# LDO-Board.net
KiCad netlist of a schematic drawn in Altium Designer
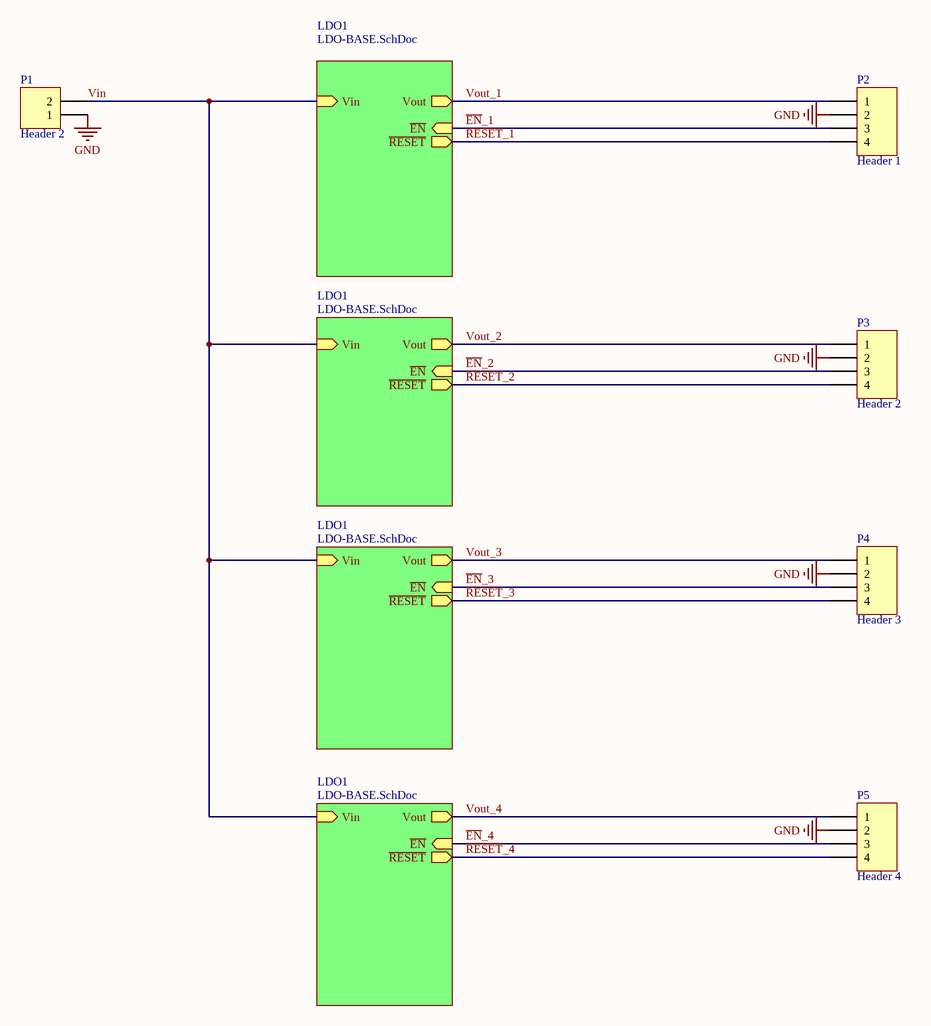
[diagram p0: LDO-Board.SchDoc]

(export (version "E")
  (design (tool "Eeschema 10.0.6"))
  (components
    (comp (ref "P1")
      (value "Header 2")
      (footprint "HDR1X2")
      (description "Header, 2-Pin")
      (fields (field (name "PUBLISHER") "Altium Limited"))
      (libsource (lib "Miscellaneous Connectors") (part "Header 2"))
    )
    (comp (ref "P2")
      (value "Header 1")
      (footprint "HDR1X4")
      (description "Header, 4-Pin")
      (fields (field (name "PUBLISHER") "Altium Limited"))
      (libsource (lib "Miscellaneous Connectors") (part "Header 4"))
    )
    (comp (ref "P3")
      (value "Header 2")
      (footprint "HDR1X4")
      (description "Header, 4-Pin")
      (fields (field (name "PUBLISHER") "Altium Limited"))
      (libsource (lib "Miscellaneous Connectors") (part "Header 4"))
    )
    (comp (ref "P4")
      (value "Header 3")
      (footprint "HDR1X4")
      (description "Header, 4-Pin")
      (fields (field (name "PUBLISHER") "Altium Limited"))
      (libsource (lib "Miscellaneous Connectors") (part "Header 4"))
    )
    (comp (ref "P5")
      (value "Header 4")
      (footprint "HDR1X4")
      (description "Header, 4-Pin")
      (fields (field (name "PUBLISHER") "Altium Limited"))
      (libsource (lib "Miscellaneous Connectors") (part "Header 4"))
    )
  )
  (nets
    (net (code "1") (name "/Vin") (class "Default")
      (node (ref "P1") (pin "2") (pinfunction "2_2") (pintype "passive"))
    )
    (net (code "2") (name "/Vout_1") (class "Default")
      (node (ref "P2") (pin "1") (pinfunction "1_1") (pintype "passive"))
    )
    (net (code "3") (name "/Vout_2") (class "Default")
      (node (ref "P3") (pin "1") (pinfunction "1_1") (pintype "passive"))
    )
    (net (code "4") (name "/Vout_3") (class "Default")
      (node (ref "P4") (pin "1") (pinfunction "1_1") (pintype "passive"))
    )
    (net (code "5") (name "/Vout_4") (class "Default")
      (node (ref "P5") (pin "1") (pinfunction "1_1") (pintype "passive"))
    )
    (net (code "6") (name "/~{EN}_1") (class "Default")
      (node (ref "P2") (pin "3") (pinfunction "3_3") (pintype "passive"))
    )
    (net (code "7") (name "/~{EN}_2") (class "Default")
      (node (ref "P3") (pin "3") (pinfunction "3_3") (pintype "passive"))
    )
    (net (code "8") (name "/~{EN}_3") (class "Default")
      (node (ref "P4") (pin "3") (pinfunction "3_3") (pintype "passive"))
    )
    (net (code "9") (name "/~{EN}_4") (class "Default")
      (node (ref "P5") (pin "3") (pinfunction "3_3") (pintype "passive"))
    )
    (net (code "10") (name "/~{RESET}_1") (class "Default")
      (node (ref "P2") (pin "4") (pinfunction "4_4") (pintype "passive"))
    )
    (net (code "11") (name "/~{RESET}_2") (class "Default")
      (node (ref "P3") (pin "4") (pinfunction "4_4") (pintype "passive"))
    )
    (net (code "12") (name "/~{RESET}_3") (class "Default")
      (node (ref "P4") (pin "4") (pinfunction "4_4") (pintype "passive"))
    )
    (net (code "13") (name "/~{RESET}_4") (class "Default")
      (node (ref "P5") (pin "4") (pinfunction "4_4") (pintype "passive"))
    )
    (net (code "14") (name "GND") (class "Default")
      (node (ref "P1") (pin "1") (pinfunction "1_1") (pintype "passive"))
      (node (ref "P2") (pin "2") (pinfunction "2_2") (pintype "passive"))
      (node (ref "P3") (pin "2") (pinfunction "2_2") (pintype "passive"))
      (node (ref "P4") (pin "2") (pinfunction "2_2") (pintype "passive"))
      (node (ref "P5") (pin "2") (pinfunction "2_2") (pintype "passive"))
    )
  )
)
